# Programming.net
KiCad netlist of a schematic drawn in Altium Designer
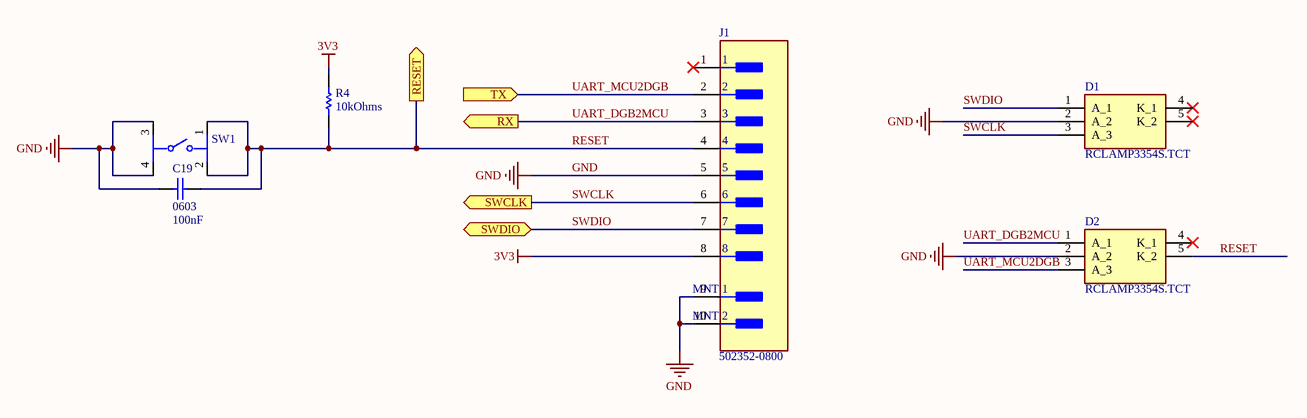
[diagram p0: Programming.SchDoc]

(export (version "E")
  (design (tool "Eeschema 10.0.6"))
  (components
    (comp (ref "C19")
      (value "C0603X104K5RACTU")
      (footprint "CAPC1608X87X35NL15T15")
      (fields
        (field (name "MANUFACTURER") "Kemet")
        (field (name "CASE CODE (IMPERIAL)") "0603")
        (field (name "CAPACITANCE") "100nF")
        (field (name "TOLERANCE") "10%")
        (field (name "VOLTAGE") "50V")
      )
      (libsource (lib "Altium Content Vault") (part "CAP"))
    )
    (comp (ref "D1")
      (value "RCLAMP3354S.TCT")
      (footprint "SamacSys:SOT95P280X145-5N")
      (description "TVS Diode (Bi-directional)")
      (fields (field (name "MOUSER PART NUMBER") "947-RCLAMP3354S.TCT"))
      (libsource (lib "*") (part "RCLAMP3354S.TCT"))
    )
    (comp (ref "D2")
      (value "RCLAMP3354S.TCT")
      (footprint "SamacSys:SOT95P280X145-5N")
      (description "TVS Diode (Bi-directional)")
      (fields (field (name "MOUSER PART NUMBER") "947-RCLAMP3354S.TCT"))
      (libsource (lib "*") (part "RCLAMP3354S.TCT"))
    )
    (comp (ref "J1")
      (value "502352-0800")
      (footprint "FP-502352-0800-MFG")
      (description "CONN HEADER SMD R/A 8POS 2MM")
      (libsource (lib "Altium Content Vault") (part "98b5586d6b3804e276fbd0410cd4945"))
    )
    (comp (ref "R4")
      (value "RC0603JR-0710KL")
      (footprint "RESC1608X55X25ML10T15")
      (description "Resistor, 10 KOhm, +/- 5%, 100 mW, -55 to 155 degC, 0603 (1608 Metric), RoHS, Tape and Reel")
      (fields
        (field (name "RESISTANCE") "10kOhms")
        (field (name "MANUFACTURER") "Yageo")
        (field (name "TOLERANCE") "5%")
      )
      (libsource (lib "Altium Content Vault") (part "RES-2"))
    )
    (comp (ref "SW1")
      (value "PTS645SM43SMTR92LFS")
      (footprint "FP-PTS645SM43SMTR92LFS-MFG")
      (description "SWITCH TACTILE SPST-NO 0.05A 12V")
      (libsource (lib "Altium Content Vault") (part "1adf0dd01260c80cf25a44bfd6b99ba"))
    )
  )
  (nets
    (net (code "1") (name "/RESET") (class "Default")
      (node (ref "C19") (pin "1") (pinfunction "1_1") (pintype "passive"))
      (node (ref "D2") (pin "5") (pinfunction "K_2_5") (pintype "passive"))
      (node (ref "J1") (pin "4") (pinfunction "4_4") (pintype "passive"))
      (node (ref "R4") (pin "1") (pinfunction "1_1") (pintype "passive"))
      (node (ref "SW1") (pin "1") (pinfunction "1_1") (pintype "passive"))
      (node (ref "SW1") (pin "2") (pinfunction "2_2") (pintype "passive"))
    )
    (net (code "2") (name "/SWCLK") (class "Default")
      (node (ref "D1") (pin "3") (pinfunction "A_3_3") (pintype "passive"))
      (node (ref "J1") (pin "6") (pinfunction "6_6") (pintype "passive"))
    )
    (net (code "3") (name "/SWDIO") (class "Default")
      (node (ref "D1") (pin "1") (pinfunction "A_1_1") (pintype "passive"))
      (node (ref "J1") (pin "7") (pinfunction "7_7") (pintype "passive"))
    )
    (net (code "4") (name "/UART_DGB2MCU") (class "Default")
      (node (ref "D2") (pin "1") (pinfunction "A_1_1") (pintype "passive"))
      (node (ref "J1") (pin "3") (pinfunction "3_3") (pintype "passive"))
    )
    (net (code "5") (name "/UART_MCU2DGB") (class "Default")
      (node (ref "D2") (pin "3") (pinfunction "A_3_3") (pintype "passive"))
      (node (ref "J1") (pin "2") (pinfunction "2_2") (pintype "passive"))
    )
    (net (code "6") (name "3V3") (class "Default")
      (node (ref "J1") (pin "8") (pinfunction "8_8") (pintype "passive"))
      (node (ref "R4") (pin "2") (pinfunction "2_2") (pintype "passive"))
    )
    (net (code "7") (name "GND") (class "Default")
      (node (ref "C19") (pin "2") (pinfunction "2_2") (pintype "passive"))
      (node (ref "D1") (pin "2") (pinfunction "A_2_2") (pintype "passive"))
      (node (ref "D2") (pin "2") (pinfunction "A_2_2") (pintype "passive"))
      (node (ref "J1") (pin "10") (pinfunction "MNT_2_10") (pintype "passive"))
      (node (ref "J1") (pin "5") (pinfunction "5_5") (pintype "passive"))
      (node (ref "J1") (pin "9") (pinfunction "MNT_1_9") (pintype "passive"))
      (node (ref "SW1") (pin "3") (pinfunction "3_3") (pintype "passive"))
      (node (ref "SW1") (pin "4") (pinfunction "4_4") (pintype "passive"))
    )
    (net (code "8") (name "unconnected-(D1-K_1-Pad4)") (class "Default")
      (node (ref "D1") (pin "4") (pinfunction "K_1_4") (pintype "passive+no_connect"))
    )
    (net (code "9") (name "unconnected-(D1-K_2-Pad5)") (class "Default")
      (node (ref "D1") (pin "5") (pinfunction "K_2_5") (pintype "passive+no_connect"))
    )
    (net (code "10") (name "unconnected-(D2-K_1-Pad4)") (class "Default")
      (node (ref "D2") (pin "4") (pinfunction "K_1_4") (pintype "passive+no_connect"))
    )
    (net (code "11") (name "unconnected-(J1-Pad1)") (class "Default")
      (node (ref "J1") (pin "1") (pinfunction "1_1") (pintype "passive+no_connect"))
    )
  )
)
